# RS485.net
KiCad netlist of a schematic drawn in Altium Designer
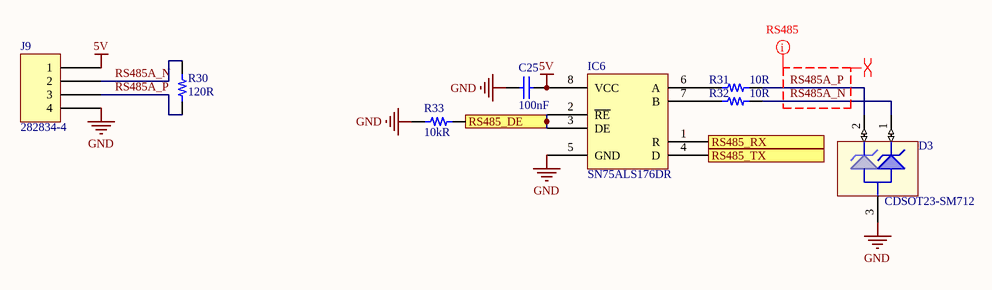
[diagram p0: RS485.SchDoc]

(export (version "E")
  (design (tool "Eeschema 10.0.6"))
  (components
    (comp (ref "C25")
      (value "100nF")
      (footprint "CAP 0603/1608")
      (description "Capacitor, Ceramic")
      (fields
        (field (name "MANUFACTURER") "Samsung")
        (field (name "MANUFACTURER PART NUMBER") "CL10A104KA8NNNC")
      )
      (libsource (lib "Muhammet_All_In_One") (part "Cap - Ceramic"))
    )
    (comp (ref "D3")
      (value "CDSOT23-SM712")
      (footprint "sc70-3")
      (description "Dual-line Transil™,  transient voltage suppressor (TVS)")
      (fields (field (name "MANUFACTURER") "Bourns"))
      (libsource (lib "Muhammet_All_In_One") (part "TVS Array"))
    )
    (comp (ref "IC6")
      (value "SN75ALS176DR")
      (footprint "TI SOIC-8 D")
      (description "IC TRANSCEIVER HALF 1/1 8SOIC")
      (fields (field (name "MANUFACTURER") "Texas Instruments"))
      (libsource (lib "Celestial Altium Library - altium_library") (part "TI SN65HVD7x"))
    )
    (comp (ref "J9")
      (value "282834-4")
      (footprint "TE 282834-4")
      (description "TERM BLK 4P SIDE ENT 2.54MM PCB")
      (fields (field (name "MANUFACTURER") "TE Connectivity AMP Connectors") (field (name "VOLTAGE") "150V"))
      (libsource (lib "Celestial Altium Library - altium_library") (part "4 Pin"))
    )
    (comp (ref "R30")
      (value "120R")
      (footprint "RES 0603/1608")
      (description "Ceramic, SMT Capacitor")
      (fields
        (field (name "MANUFACTURER") "Susumu")
        (field (name "MANUFACTURER PART NUMBER") "RR0816P-121-D")
      )
      (libsource (lib "yildizIoT Library") (part "Resistor_Chip"))
    )
    (comp (ref "R31")
      (value "10R")
      (footprint "RES 0603/1608")
      (description "Ceramic, SMT Capacitor")
      (fields (field (name "MANUFACTURER") "Rohm") (field (name "MANUFACTURER PART NUMBER") "ESR03EZPJ100"))
      (libsource (lib "yildizIoT Library") (part "Resistor_Chip"))
    )
    (comp (ref "R32")
      (value "10R")
      (footprint "RES 0603/1608")
      (description "Ceramic, SMT Capacitor")
      (fields (field (name "MANUFACTURER") "Rohm") (field (name "MANUFACTURER PART NUMBER") "ESR03EZPJ100"))
      (libsource (lib "yildizIoT Library") (part "Resistor_Chip"))
    )
    (comp (ref "R33")
      (value "10kR")
      (footprint "RES 0603/1608")
      (description "Ceramic, SMT Capacitor")
      (fields
        (field (name "MANUFACTURER") "Stackpole Electronics")
        (field (name "MANUFACTURER PART NUMBER") "RNCP0603FTD10K0")
      )
      (libsource (lib "yildizIoT Library") (part "Resistor_Chip"))
    )
  )
  (nets
    (net (code "1") (name "/RS485A_N") (class "Default")
      (node (ref "D3") (pin "1") (pinfunction "1_1") (pintype "bidirectional"))
      (node (ref "J9") (pin "2") (pinfunction "2_2") (pintype "passive"))
      (node (ref "R30") (pin "2") (pinfunction "2_2") (pintype "passive"))
      (node (ref "R32") (pin "2") (pinfunction "2_2") (pintype "passive"))
    )
    (net (code "2") (name "/RS485A_P") (class "Default")
      (node (ref "D3") (pin "2") (pinfunction "2_2") (pintype "bidirectional"))
      (node (ref "J9") (pin "3") (pinfunction "3_3") (pintype "passive"))
      (node (ref "R30") (pin "1") (pinfunction "1_1") (pintype "passive"))
      (node (ref "R31") (pin "2") (pinfunction "2_2") (pintype "passive"))
    )
    (net (code "3") (name "/RS485_DE") (class "Default")
      (node (ref "IC6") (pin "2") (pinfunction "~{RE}_2") (pintype "passive"))
      (node (ref "IC6") (pin "3") (pinfunction "DE_3") (pintype "passive"))
      (node (ref "R33") (pin "1") (pinfunction "1_1") (pintype "passive"))
    )
    (net (code "4") (name "/RS485_RX") (class "Default")
      (node (ref "IC6") (pin "1") (pinfunction "R_1") (pintype "passive"))
    )
    (net (code "5") (name "/RS485_TX") (class "Default")
      (node (ref "IC6") (pin "4") (pinfunction "D_4") (pintype "passive"))
    )
    (net (code "6") (name "5V") (class "Default")
      (node (ref "C25") (pin "2") (pinfunction "2_2") (pintype "passive"))
      (node (ref "IC6") (pin "8") (pinfunction "VCC_8") (pintype "passive"))
      (node (ref "J9") (pin "1") (pinfunction "1_1") (pintype "passive"))
    )
    (net (code "7") (name "GND") (class "Default")
      (node (ref "C25") (pin "1") (pinfunction "1_1") (pintype "passive"))
      (node (ref "D3") (pin "3") (pinfunction "3_3") (pintype "power_in"))
      (node (ref "IC6") (pin "5") (pinfunction "GND_5") (pintype "passive"))
      (node (ref "J9") (pin "4") (pinfunction "4_4") (pintype "passive"))
      (node (ref "R33") (pin "2") (pinfunction "2_2") (pintype "passive"))
    )
    (net (code "8") (name "Net-(IC6-A)") (class "Default")
      (node (ref "IC6") (pin "6") (pinfunction "A_6") (pintype "passive"))
      (node (ref "R31") (pin "1") (pinfunction "1_1") (pintype "passive"))
    )
    (net (code "9") (name "Net-(IC6-B)") (class "Default")
      (node (ref "IC6") (pin "7") (pinfunction "B_7") (pintype "passive"))
      (node (ref "R32") (pin "1") (pinfunction "1_1") (pintype "passive"))
    )
  )
)
